# hellobusnode.net
KiCad netlist of a schematic drawn in EAGLE
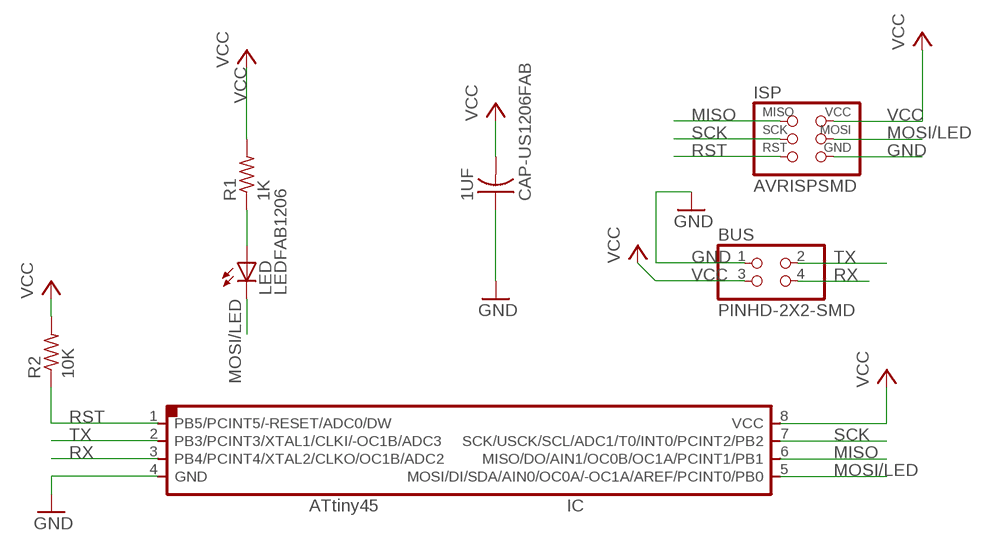
[diagram p0: schematic, sheet 1]

(export (version "E")
  (design (tool "Eeschema 10.0.6"))
  (components
    (comp (ref "1UF")
      (value "CAP-US1206FAB")
      (footprint "eagle-import:C1206FAB")
      (libsource (lib "eagle-import") (part "CAP-US1206FAB"))
    )
    (comp (ref "BUS")
      (value "PINHD-2X2-SMD")
      (footprint "eagle-import:2X02SMD")
      (libsource (lib "eagle-import") (part "PINHD-2X2-SMD"))
    )
    (comp (ref "IC")
      (value "IC")
      (footprint "eagle-import:SOIC8")
      (libsource (lib "eagle-import") (part "ATTINY45SI"))
    )
    (comp (ref "ISP")
      (value "AVRISPSMD")
      (footprint "eagle-import:2X03SMD")
      (libsource (lib "eagle-import") (part "AVRISPSMD"))
    )
    (comp (ref "LED")
      (value "LEDFAB1206")
      (footprint "eagle-import:LED1206FAB")
      (libsource (lib "eagle-import") (part "LEDFAB1206"))
    )
    (comp (ref "R1")
      (value "1K")
      (footprint "eagle-import:R1206FAB")
      (libsource (lib "eagle-import") (part "RES-US1206FAB"))
    )
    (comp (ref "R2")
      (value "10K")
      (footprint "eagle-import:R1206FAB")
      (libsource (lib "eagle-import") (part "RES-US1206FAB"))
    )
  )
  (nets
    (net (code "1") (name "/MISO") (class "Default")
      (node (ref "IC") (pin "6") (pinfunction "MISO/DO/AIN1/OC0B/OC1A/PCINT1/PB1_6") (pintype "bidirectional"))
      (node (ref "ISP") (pin "1") (pinfunction "MISO_1") (pintype "passive"))
    )
    (net (code "2") (name "/MOSI{slash}LED") (class "Default")
      (node (ref "IC") (pin "5") (pinfunction "MOSI/DI/SDA/AIN0/OC0A/-OC1A/AREF/PCINT0/PB0_5") (pintype "bidirectional"))
      (node (ref "ISP") (pin "4") (pinfunction "MOSI_4") (pintype "passive"))
      (node (ref "LED") (pin "2") (pinfunction "C_2") (pintype "passive"))
    )
    (net (code "3") (name "/RST") (class "Default")
      (node (ref "IC") (pin "1") (pinfunction "PB5/PCINT5/-RESET/ADC0/DW_1") (pintype "bidirectional"))
      (node (ref "ISP") (pin "5") (pinfunction "RST_5") (pintype "passive"))
      (node (ref "R2") (pin "1") (pinfunction "1_1") (pintype "passive"))
    )
    (net (code "4") (name "/RX") (class "Default")
      (node (ref "BUS") (pin "4") (pinfunction "4_4") (pintype "passive"))
      (node (ref "IC") (pin "3") (pinfunction "PB4/PCINT4/XTAL2/CLKO/OC1B/ADC2_3") (pintype "bidirectional"))
    )
    (net (code "5") (name "/SCK") (class "Default")
      (node (ref "IC") (pin "7") (pinfunction "SCK/USCK/SCL/ADC1/T0/INT0/PCINT2/PB2_7") (pintype "bidirectional"))
      (node (ref "ISP") (pin "3") (pinfunction "SCK_3") (pintype "passive"))
    )
    (net (code "6") (name "/TX") (class "Default")
      (node (ref "BUS") (pin "2") (pinfunction "2_2") (pintype "passive"))
      (node (ref "IC") (pin "2") (pinfunction "PB3/PCINT3/XTAL1/CLKI/-OC1B/ADC3_2") (pintype "bidirectional"))
    )
    (net (code "7") (name "GND") (class "Default")
      (node (ref "1UF") (pin "1") (pinfunction "1_1") (pintype "passive"))
      (node (ref "BUS") (pin "1") (pinfunction "1_1") (pintype "passive"))
      (node (ref "IC") (pin "4") (pinfunction "GND_4") (pintype "bidirectional"))
      (node (ref "ISP") (pin "6") (pinfunction "GND_6") (pintype "passive"))
    )
    (net (code "8") (name "Net-(LED-A)") (class "Default")
      (node (ref "LED") (pin "1") (pinfunction "A_1") (pintype "passive"))
      (node (ref "R1") (pin "1") (pinfunction "1_1") (pintype "passive"))
    )
    (net (code "9") (name "VCC") (class "Default")
      (node (ref "1UF") (pin "2") (pinfunction "2_2") (pintype "passive"))
      (node (ref "BUS") (pin "3") (pinfunction "3_3") (pintype "passive"))
      (node (ref "IC") (pin "8") (pinfunction "VCC_8") (pintype "bidirectional"))
      (node (ref "ISP") (pin "2") (pinfunction "VCC_2") (pintype "passive"))
      (node (ref "R1") (pin "2") (pinfunction "2_2") (pintype "passive"))
      (node (ref "R2") (pin "2") (pinfunction "2_2") (pintype "passive"))
    )
  )
)
